# pcb.net
KiCad netlist of a schematic drawn in EAGLE
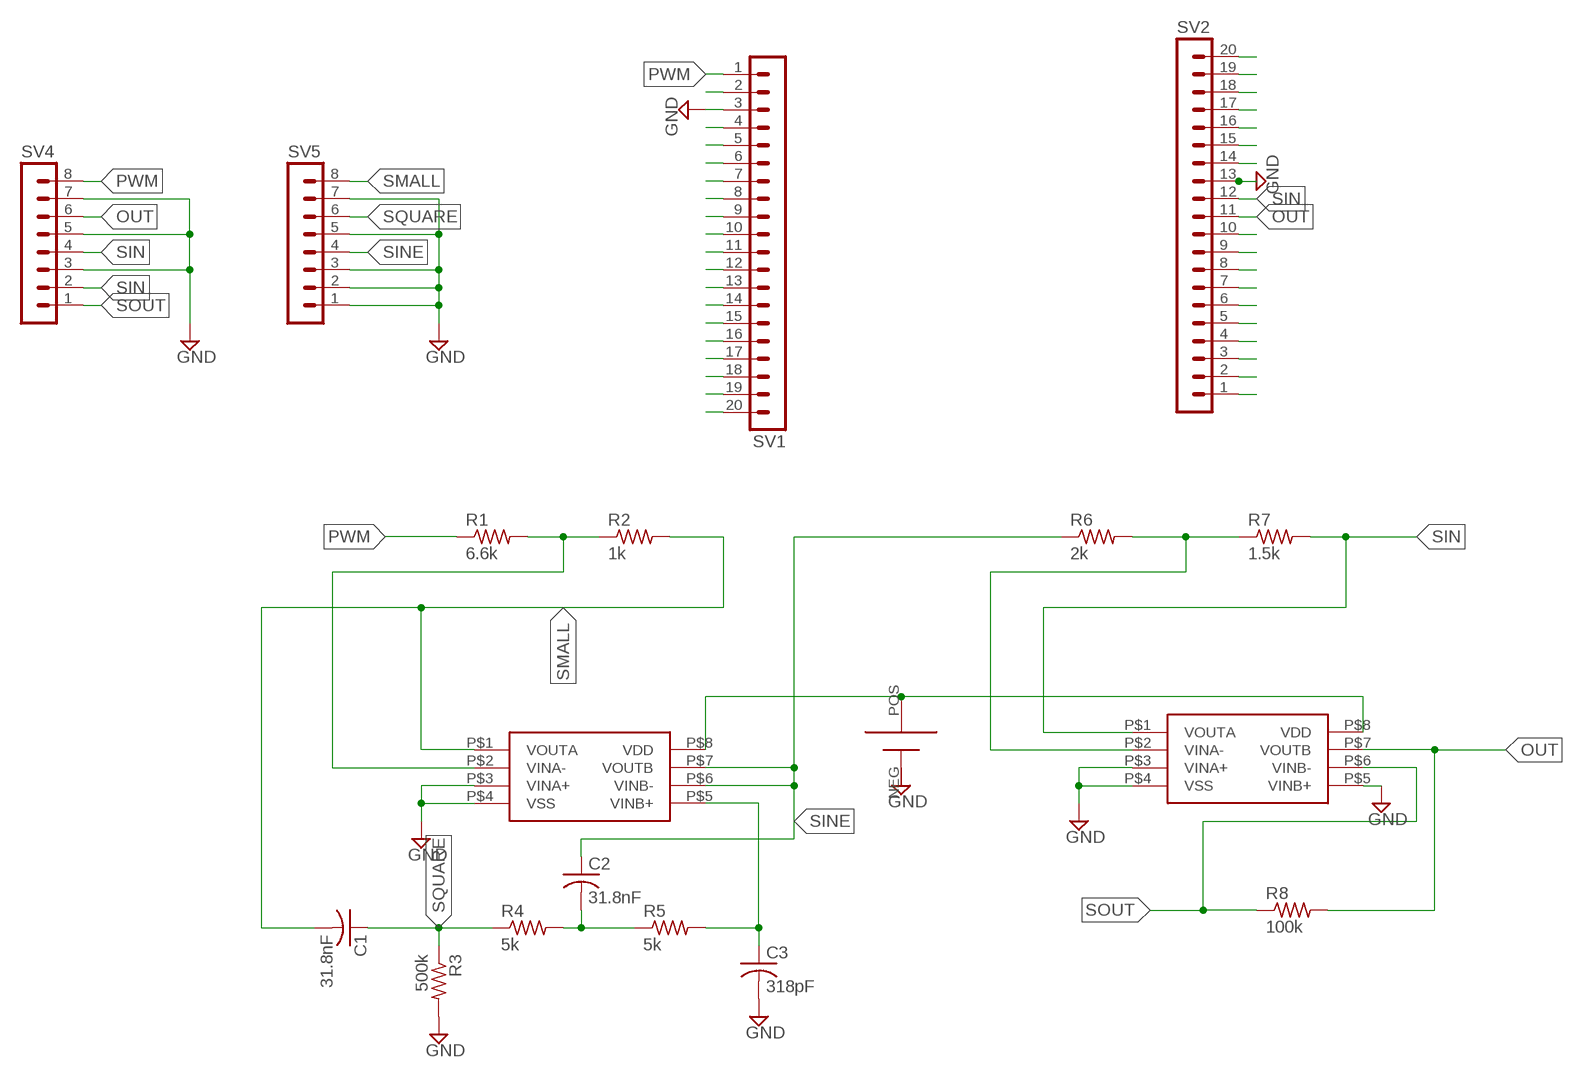
[diagram p0: schematic, sheet 1]

(export (version "E")
  (design (tool "Eeschema 10.0.6"))
  (components
    (comp (ref "C1")
      (value "31.8nF")
      (footprint "eagle-import:C0603")
      (libsource (lib "eagle-import") (part "C-USC0603"))
    )
    (comp (ref "C2")
      (value "31.8nF")
      (footprint "eagle-import:C0603")
      (libsource (lib "eagle-import") (part "C-USC0603"))
    )
    (comp (ref "C3")
      (value "318pF")
      (footprint "eagle-import:C0603")
      (libsource (lib "eagle-import") (part "C-USC0603"))
    )
    (comp (ref "R1")
      (value "6.6k")
      (footprint "eagle-import:R0603")
      (libsource (lib "eagle-import") (part "R-US_R0603"))
    )
    (comp (ref "R2")
      (value "1k")
      (footprint "eagle-import:R0603")
      (libsource (lib "eagle-import") (part "R-US_R0603"))
    )
    (comp (ref "R3")
      (value "500k")
      (footprint "eagle-import:R0603")
      (libsource (lib "eagle-import") (part "R-US_R0603"))
    )
    (comp (ref "R4")
      (value "5k")
      (footprint "eagle-import:R0603")
      (libsource (lib "eagle-import") (part "R-US_R0603"))
    )
    (comp (ref "R5")
      (value "5k")
      (footprint "eagle-import:R0603")
      (libsource (lib "eagle-import") (part "R-US_R0603"))
    )
    (comp (ref "R6")
      (value "2k")
      (footprint "eagle-import:R0603")
      (libsource (lib "eagle-import") (part "R-US_R0603"))
    )
    (comp (ref "R7")
      (value "1.5k")
      (footprint "eagle-import:R0603")
      (libsource (lib "eagle-import") (part "R-US_R0603"))
    )
    (comp (ref "R8")
      (value "100k")
      (footprint "eagle-import:R0603")
      (libsource (lib "eagle-import") (part "R-US_R0603"))
    )
    (comp (ref "SV1")
      (value "MA20-1")
      (footprint "eagle-import:MA20-1")
      (libsource (lib "eagle-import") (part "MA20-1"))
    )
    (comp (ref "SV2")
      (value "MA20-1")
      (footprint "eagle-import:MA20-1")
      (libsource (lib "eagle-import") (part "MA20-1"))
    )
    (comp (ref "SV4")
      (value "MA08-1")
      (footprint "eagle-import:MA08-1")
      (libsource (lib "eagle-import") (part "MA08-1"))
    )
    (comp (ref "SV5")
      (value "MA08-1")
      (footprint "eagle-import:MA08-1")
      (libsource (lib "eagle-import") (part "MA08-1"))
    )
    (comp (ref "U$1")
      (value "BH80A1")
      (footprint "eagle-import:BH80A1")
      (libsource (lib "eagle-import") (part "BH80A1"))
    )
    (comp (ref "U$3")
      (value "MCP6V12")
      (footprint "eagle-import:MCP6V12MSOP8")
      (libsource (lib "eagle-import") (part "MCP6V12"))
    )
    (comp (ref "U$4")
      (value "MCP6V12")
      (footprint "eagle-import:MCP6V12MSOP8")
      (libsource (lib "eagle-import") (part "MCP6V12"))
    )
  )
  (nets
    (net (code "1") (name "/NEG") (class "Default")
      (node (ref "U$1") (pin "NEG") (pinfunction "NEG_NEG") (pintype "power_in"))
    )
    (net (code "2") (name "GND") (class "Default")
      (node (ref "C3") (pin "2") (pinfunction "2_2") (pintype "passive"))
      (node (ref "R3") (pin "2") (pinfunction "2_2") (pintype "passive"))
      (node (ref "SV1") (pin "3") (pinfunction "3_3") (pintype "passive"))
      (node (ref "SV2") (pin "13") (pinfunction "13_13") (pintype "passive"))
      (node (ref "SV4") (pin "3") (pinfunction "3_3") (pintype "passive"))
      (node (ref "SV4") (pin "5") (pinfunction "5_5") (pintype "passive"))
      (node (ref "SV4") (pin "7") (pinfunction "7_7") (pintype "passive"))
      (node (ref "SV5") (pin "1") (pinfunction "1_1") (pintype "passive"))
      (node (ref "SV5") (pin "2") (pinfunction "2_2") (pintype "passive"))
      (node (ref "SV5") (pin "3") (pinfunction "3_3") (pintype "passive"))
      (node (ref "SV5") (pin "5") (pinfunction "5_5") (pintype "passive"))
      (node (ref "SV5") (pin "7") (pinfunction "7_7") (pintype "passive"))
      (node (ref "U$3") (pin "P$3") (pinfunction "VINA+_P$3") (pintype "bidirectional"))
      (node (ref "U$3") (pin "P$4") (pinfunction "VSS_P$4") (pintype "bidirectional"))
      (node (ref "U$4") (pin "P$3") (pinfunction "VINA+_P$3") (pintype "bidirectional"))
      (node (ref "U$4") (pin "P$4") (pinfunction "VSS_P$4") (pintype "bidirectional"))
      (node (ref "U$4") (pin "P$5") (pinfunction "VINB+_P$5") (pintype "bidirectional"))
    )
    (net (code "3") (name "Net-(C2-Pad2)") (class "Default")
      (node (ref "C2") (pin "2") (pinfunction "2_2") (pintype "passive"))
      (node (ref "R4") (pin "2") (pinfunction "2_2") (pintype "passive"))
      (node (ref "R5") (pin "1") (pinfunction "1_1") (pintype "passive"))
    )
    (net (code "4") (name "Net-(U$3-VDD)") (class "Default")
      (node (ref "U$1") (pin "POS") (pinfunction "POS_POS") (pintype "power_in"))
      (node (ref "U$3") (pin "P$8") (pinfunction "VDD_P$8") (pintype "bidirectional"))
      (node (ref "U$4") (pin "P$8") (pinfunction "VDD_P$8") (pintype "bidirectional"))
    )
    (net (code "5") (name "Net-(U$3-VINA-)") (class "Default")
      (node (ref "R1") (pin "2") (pinfunction "2_2") (pintype "passive"))
      (node (ref "R2") (pin "1") (pinfunction "1_1") (pintype "passive"))
      (node (ref "U$3") (pin "P$2") (pinfunction "VINA-_P$2") (pintype "bidirectional"))
    )
    (net (code "6") (name "Net-(U$3-VINB+)") (class "Default")
      (node (ref "C3") (pin "1") (pinfunction "1_1") (pintype "passive"))
      (node (ref "R5") (pin "2") (pinfunction "2_2") (pintype "passive"))
      (node (ref "U$3") (pin "P$5") (pinfunction "VINB+_P$5") (pintype "bidirectional"))
    )
    (net (code "7") (name "Net-(U$4-VINA-)") (class "Default")
      (node (ref "R6") (pin "2") (pinfunction "2_2") (pintype "passive"))
      (node (ref "R7") (pin "1") (pinfunction "1_1") (pintype "passive"))
      (node (ref "U$4") (pin "P$2") (pinfunction "VINA-_P$2") (pintype "bidirectional"))
    )
    (net (code "8") (name "OUT") (class "Default")
      (node (ref "R8") (pin "2") (pinfunction "2_2") (pintype "passive"))
      (node (ref "SV2") (pin "11") (pinfunction "11_11") (pintype "passive"))
      (node (ref "SV4") (pin "6") (pinfunction "6_6") (pintype "passive"))
      (node (ref "U$4") (pin "P$7") (pinfunction "VOUTB_P$7") (pintype "bidirectional"))
    )
    (net (code "9") (name "PWM") (class "Default")
      (node (ref "R1") (pin "1") (pinfunction "1_1") (pintype "passive"))
      (node (ref "SV1") (pin "1") (pinfunction "1_1") (pintype "passive"))
      (node (ref "SV4") (pin "8") (pinfunction "8_8") (pintype "passive"))
    )
    (net (code "10") (name "SIN") (class "Default")
      (node (ref "R7") (pin "2") (pinfunction "2_2") (pintype "passive"))
      (node (ref "SV2") (pin "12") (pinfunction "12_12") (pintype "passive"))
      (node (ref "SV4") (pin "2") (pinfunction "2_2") (pintype "passive"))
      (node (ref "SV4") (pin "4") (pinfunction "4_4") (pintype "passive"))
      (node (ref "U$4") (pin "P$1") (pinfunction "VOUTA_P$1") (pintype "bidirectional"))
    )
    (net (code "11") (name "SINE") (class "Default")
      (node (ref "C2") (pin "1") (pinfunction "1_1") (pintype "passive"))
      (node (ref "R6") (pin "1") (pinfunction "1_1") (pintype "passive"))
      (node (ref "SV5") (pin "4") (pinfunction "4_4") (pintype "passive"))
      (node (ref "U$3") (pin "P$6") (pinfunction "VINB-_P$6") (pintype "bidirectional"))
      (node (ref "U$3") (pin "P$7") (pinfunction "VOUTB_P$7") (pintype "bidirectional"))
    )
    (net (code "12") (name "SMALL") (class "Default")
      (node (ref "C1") (pin "2") (pinfunction "2_2") (pintype "passive"))
      (node (ref "R2") (pin "2") (pinfunction "2_2") (pintype "passive"))
      (node (ref "SV5") (pin "8") (pinfunction "8_8") (pintype "passive"))
      (node (ref "U$3") (pin "P$1") (pinfunction "VOUTA_P$1") (pintype "bidirectional"))
    )
    (net (code "13") (name "SOUT") (class "Default")
      (node (ref "R8") (pin "1") (pinfunction "1_1") (pintype "passive"))
      (node (ref "SV4") (pin "1") (pinfunction "1_1") (pintype "passive"))
      (node (ref "U$4") (pin "P$6") (pinfunction "VINB-_P$6") (pintype "bidirectional"))
    )
    (net (code "14") (name "SQUARE") (class "Default")
      (node (ref "C1") (pin "1") (pinfunction "1_1") (pintype "passive"))
      (node (ref "R3") (pin "1") (pinfunction "1_1") (pintype "passive"))
      (node (ref "R4") (pin "1") (pinfunction "1_1") (pintype "passive"))
      (node (ref "SV5") (pin "6") (pinfunction "6_6") (pintype "passive"))
    )
    (net (code "15") (name "unconnected-(SV1-Pad2)") (class "Default")
      (node (ref "SV1") (pin "2") (pinfunction "2_2") (pintype "passive"))
    )
    (net (code "16") (name "unconnected-(SV1-Pad4)") (class "Default")
      (node (ref "SV1") (pin "4") (pinfunction "4_4") (pintype "passive"))
    )
    (net (code "17") (name "unconnected-(SV1-Pad5)") (class "Default")
      (node (ref "SV1") (pin "5") (pinfunction "5_5") (pintype "passive"))
    )
    (net (code "18") (name "unconnected-(SV1-Pad6)") (class "Default")
      (node (ref "SV1") (pin "6") (pinfunction "6_6") (pintype "passive"))
    )
    (net (code "19") (name "unconnected-(SV1-Pad7)") (class "Default")
      (node (ref "SV1") (pin "7") (pinfunction "7_7") (pintype "passive"))
    )
    (net (code "20") (name "unconnected-(SV1-Pad8)") (class "Default")
      (node (ref "SV1") (pin "8") (pinfunction "8_8") (pintype "passive"))
    )
    (net (code "21") (name "unconnected-(SV1-Pad9)") (class "Default")
      (node (ref "SV1") (pin "9") (pinfunction "9_9") (pintype "passive"))
    )
    (net (code "22") (name "unconnected-(SV1-Pad10)") (class "Default")
      (node (ref "SV1") (pin "10") (pinfunction "10_10") (pintype "passive"))
    )
    (net (code "23") (name "unconnected-(SV1-Pad11)") (class "Default")
      (node (ref "SV1") (pin "11") (pinfunction "11_11") (pintype "passive"))
    )
    (net (code "24") (name "unconnected-(SV1-Pad12)") (class "Default")
      (node (ref "SV1") (pin "12") (pinfunction "12_12") (pintype "passive"))
    )
    (net (code "25") (name "unconnected-(SV1-Pad13)") (class "Default")
      (node (ref "SV1") (pin "13") (pinfunction "13_13") (pintype "passive"))
    )
    (net (code "26") (name "unconnected-(SV1-Pad14)") (class "Default")
      (node (ref "SV1") (pin "14") (pinfunction "14_14") (pintype "passive"))
    )
    (net (code "27") (name "unconnected-(SV1-Pad15)") (class "Default")
      (node (ref "SV1") (pin "15") (pinfunction "15_15") (pintype "passive"))
    )
    (net (code "28") (name "unconnected-(SV1-Pad16)") (class "Default")
      (node (ref "SV1") (pin "16") (pinfunction "16_16") (pintype "passive"))
    )
    (net (code "29") (name "unconnected-(SV1-Pad17)") (class "Default")
      (node (ref "SV1") (pin "17") (pinfunction "17_17") (pintype "passive"))
    )
    (net (code "30") (name "unconnected-(SV1-Pad18)") (class "Default")
      (node (ref "SV1") (pin "18") (pinfunction "18_18") (pintype "passive"))
    )
    (net (code "31") (name "unconnected-(SV1-Pad19)") (class "Default")
      (node (ref "SV1") (pin "19") (pinfunction "19_19") (pintype "passive"))
    )
    (net (code "32") (name "unconnected-(SV1-Pad20)") (class "Default")
      (node (ref "SV1") (pin "20") (pinfunction "20_20") (pintype "passive"))
    )
    (net (code "33") (name "unconnected-(SV2-Pad1)") (class "Default")
      (node (ref "SV2") (pin "1") (pinfunction "1_1") (pintype "passive"))
    )
    (net (code "34") (name "unconnected-(SV2-Pad2)") (class "Default")
      (node (ref "SV2") (pin "2") (pinfunction "2_2") (pintype "passive"))
    )
    (net (code "35") (name "unconnected-(SV2-Pad3)") (class "Default")
      (node (ref "SV2") (pin "3") (pinfunction "3_3") (pintype "passive"))
    )
    (net (code "36") (name "unconnected-(SV2-Pad4)") (class "Default")
      (node (ref "SV2") (pin "4") (pinfunction "4_4") (pintype "passive"))
    )
    (net (code "37") (name "unconnected-(SV2-Pad5)") (class "Default")
      (node (ref "SV2") (pin "5") (pinfunction "5_5") (pintype "passive"))
    )
    (net (code "38") (name "unconnected-(SV2-Pad6)") (class "Default")
      (node (ref "SV2") (pin "6") (pinfunction "6_6") (pintype "passive"))
    )
    (net (code "39") (name "unconnected-(SV2-Pad7)") (class "Default")
      (node (ref "SV2") (pin "7") (pinfunction "7_7") (pintype "passive"))
    )
    (net (code "40") (name "unconnected-(SV2-Pad8)") (class "Default")
      (node (ref "SV2") (pin "8") (pinfunction "8_8") (pintype "passive"))
    )
    (net (code "41") (name "unconnected-(SV2-Pad9)") (class "Default")
      (node (ref "SV2") (pin "9") (pinfunction "9_9") (pintype "passive"))
    )
    (net (code "42") (name "unconnected-(SV2-Pad10)") (class "Default")
      (node (ref "SV2") (pin "10") (pinfunction "10_10") (pintype "passive"))
    )
    (net (code "43") (name "unconnected-(SV2-Pad14)") (class "Default")
      (node (ref "SV2") (pin "14") (pinfunction "14_14") (pintype "passive"))
    )
    (net (code "44") (name "unconnected-(SV2-Pad15)") (class "Default")
      (node (ref "SV2") (pin "15") (pinfunction "15_15") (pintype "passive"))
    )
    (net (code "45") (name "unconnected-(SV2-Pad16)") (class "Default")
      (node (ref "SV2") (pin "16") (pinfunction "16_16") (pintype "passive"))
    )
    (net (code "46") (name "unconnected-(SV2-Pad17)") (class "Default")
      (node (ref "SV2") (pin "17") (pinfunction "17_17") (pintype "passive"))
    )
    (net (code "47") (name "unconnected-(SV2-Pad18)") (class "Default")
      (node (ref "SV2") (pin "18") (pinfunction "18_18") (pintype "passive"))
    )
    (net (code "48") (name "unconnected-(SV2-Pad19)") (class "Default")
      (node (ref "SV2") (pin "19") (pinfunction "19_19") (pintype "passive"))
    )
    (net (code "49") (name "unconnected-(SV2-Pad20)") (class "Default")
      (node (ref "SV2") (pin "20") (pinfunction "20_20") (pintype "passive"))
    )
  )
)
